# VRef_2.net
KiCad netlist of a schematic drawn in Altium Designer
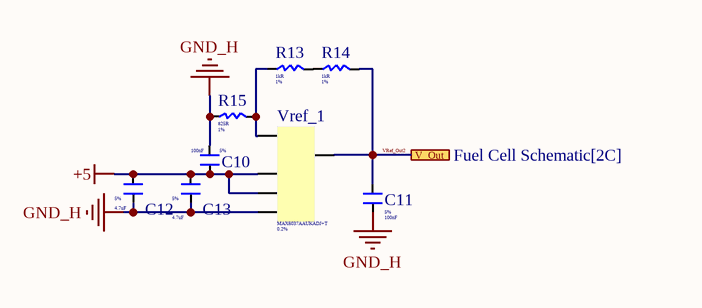
[diagram p0: VRef_2.SchDoc]

(export (version "E")
  (design (tool "Eeschema 10.0.6"))
  (components
    (comp (ref "C10")
      (value "~")
      (footprint "Capacitor_Kemet_0805")
      (description "Cap Ceramic 0.1uF 16V X7R 5% SMD 0805 125°C Plastic T/R")
      (fields
        (field (name "MANUFACTURER") "KEMET")
        (field (name "MANUFACTURER PART NUMBER") "C0805C104J4RACTU")
        (field (name "DISSIPATION FACTOR") "5%")
        (field (name "CAPACITANCE") "100nF")
      )
      (libsource (lib "Schlib1") (part "C0805C104J4RACTU"))
    )
    (comp (ref "C11")
      (value "~")
      (footprint "Capacitor_Kemet_0805")
      (description "Cap Ceramic 0.1uF 16V X7R 5% SMD 0805 125°C Plastic T/R")
      (fields
        (field (name "MANUFACTURER") "KEMET")
        (field (name "MANUFACTURER PART NUMBER") "C0805C104J4RACTU")
        (field (name "DISSIPATION FACTOR") "5%")
        (field (name "CAPACITANCE") "100nF")
      )
      (libsource (lib "Schlib1") (part "C0805C104J4RACTU"))
    )
    (comp (ref "C12")
      (value "~")
      (footprint "Capacitor_Kemet_0805")
      (description "CAP CER 4.7UF 16V X7R 0805")
      (fields
        (field (name "MANUFACTURER") "KEMET")
        (field (name "MANUFACTURER PART NUMBER") "C0805C475J4RACAUTO")
        (field (name "TOLERANCE") "5%")
        (field (name "CAPACITANCE") "4.7uF")
      )
      (libsource (lib "Schlib1") (part "C0805C475J4RACAUTO"))
    )
    (comp (ref "C13")
      (value "~")
      (footprint "Capacitor_Kemet_0805")
      (description "CAP CER 4.7UF 16V X7R 0805")
      (fields
        (field (name "MANUFACTURER") "KEMET")
        (field (name "MANUFACTURER PART NUMBER") "C0805C475J4RACAUTO")
        (field (name "TOLERANCE") "5%")
        (field (name "CAPACITANCE") "4.7uF")
      )
      (libsource (lib "Schlib1") (part "C0805C475J4RACAUTO"))
    )
    (comp (ref "R13")
      (value "~")
      (footprint "Resistor_YAGEO_0805")
      (description "Res Thick Film 0805 1K Ohm 1% 0.125W(1/8W) ±100ppm/C Pad SMD T/R")
      (fields
        (field (name "MANUFACTURER") "Yageo")
        (field (name "MANUFACTURER PART NUMBER") "RC0805FR-071KP")
        (field (name "RESISTANCE") "1kR")
        (field (name "TOLERANCE") "1%")
      )
      (libsource (lib "Schlib1") (part "RC0805FR-071KP"))
    )
    (comp (ref "R14")
      (value "~")
      (footprint "Resistor_YAGEO_0805")
      (description "Res Thick Film 0805 1K Ohm 1% 0.125W(1/8W) ±100ppm/C Pad SMD T/R")
      (fields
        (field (name "MANUFACTURER") "Yageo")
        (field (name "MANUFACTURER PART NUMBER") "RC0805FR-071KP")
        (field (name "RESISTANCE") "1kR")
        (field (name "TOLERANCE") "1%")
      )
      (libsource (lib "Schlib1") (part "RC0805FR-071KP"))
    )
    (comp (ref "R15")
      (value "~")
      (footprint "Resistor_YAGEO_0805")
      (description "825 Ohms ±1% 0.125W, 1/8W Chip Resistor 0805 (2012 Metric) Moisture Resistant Thick Film")
      (fields
        (field (name "MANUFACTURER") "Yageo")
        (field (name "MANUFACTURER PART NUMBER") "RC0805FR-07825RL")
        (field (name "RESISTANCE") "825R")
        (field (name "TOLERANCE") "1%")
      )
      (libsource (lib "Schlib1") (part "RC0805FR-07825RL"))
    )
    (comp (ref "Vref_1")
      (value "~")
      (footprint "VRef")
      (description "IC VREF SERIES ADJ 0.2% SOT23-5")
      (fields
        (field (name "MANUFACTURER") "Maxim")
        (field (name "MANUFACTURER PART NUMBER") "MAX6037AAUKADJ+T")
        (field (name "TOLERANCE") "0.2%")
      )
      (libsource (lib "Schlib1") (part "MAX6037AAUKADJ+T"))
    )
  )
  (nets
    (net (code "1") (name "+5") (class "Default")
      (node (ref "C10") (pin "1") (pinfunction "1_1") (pintype "passive"))
      (node (ref "C12") (pin "2") (pinfunction "2_2") (pintype "passive"))
      (node (ref "C13") (pin "2") (pinfunction "2_2") (pintype "passive"))
      (node (ref "Vref_1") (pin "3") (pinfunction "SHDN_3") (pintype "passive"))
      (node (ref "Vref_1") (pin "4") (pinfunction "In_4") (pintype "passive"))
    )
    (net (code "2") (name "/VRef_Out2") (class "Default")
      (node (ref "C11") (pin "2") (pinfunction "2_2") (pintype "passive"))
      (node (ref "R14") (pin "2") (pinfunction "2_2") (pintype "passive"))
      (node (ref "Vref_1") (pin "5") (pinfunction "OUT_5") (pintype "passive"))
    )
    (net (code "3") (name "GND_H") (class "Default")
      (node (ref "C10") (pin "2") (pinfunction "2_2") (pintype "passive"))
      (node (ref "C11") (pin "1") (pinfunction "1_1") (pintype "passive"))
      (node (ref "C12") (pin "1") (pinfunction "1_1") (pintype "passive"))
      (node (ref "C13") (pin "1") (pinfunction "1_1") (pintype "passive"))
      (node (ref "R15") (pin "1") (pinfunction "1_1") (pintype "passive"))
      (node (ref "Vref_1") (pin "2") (pinfunction "GND_2") (pintype "passive"))
    )
    (net (code "4") (name "Net-(R13-Pad2)") (class "Default")
      (node (ref "R13") (pin "2") (pinfunction "2_2") (pintype "passive"))
      (node (ref "R14") (pin "1") (pinfunction "1_1") (pintype "passive"))
    )
    (net (code "5") (name "Net-(Vref_1-ADJ)") (class "Default")
      (node (ref "R13") (pin "1") (pinfunction "1_1") (pintype "passive"))
      (node (ref "R15") (pin "2") (pinfunction "2_2") (pintype "passive"))
      (node (ref "Vref_1") (pin "1") (pinfunction "ADJ_1") (pintype "passive"))
    )
  )
)
